# Current_Sense.net
KiCad netlist of a schematic drawn in Altium Designer
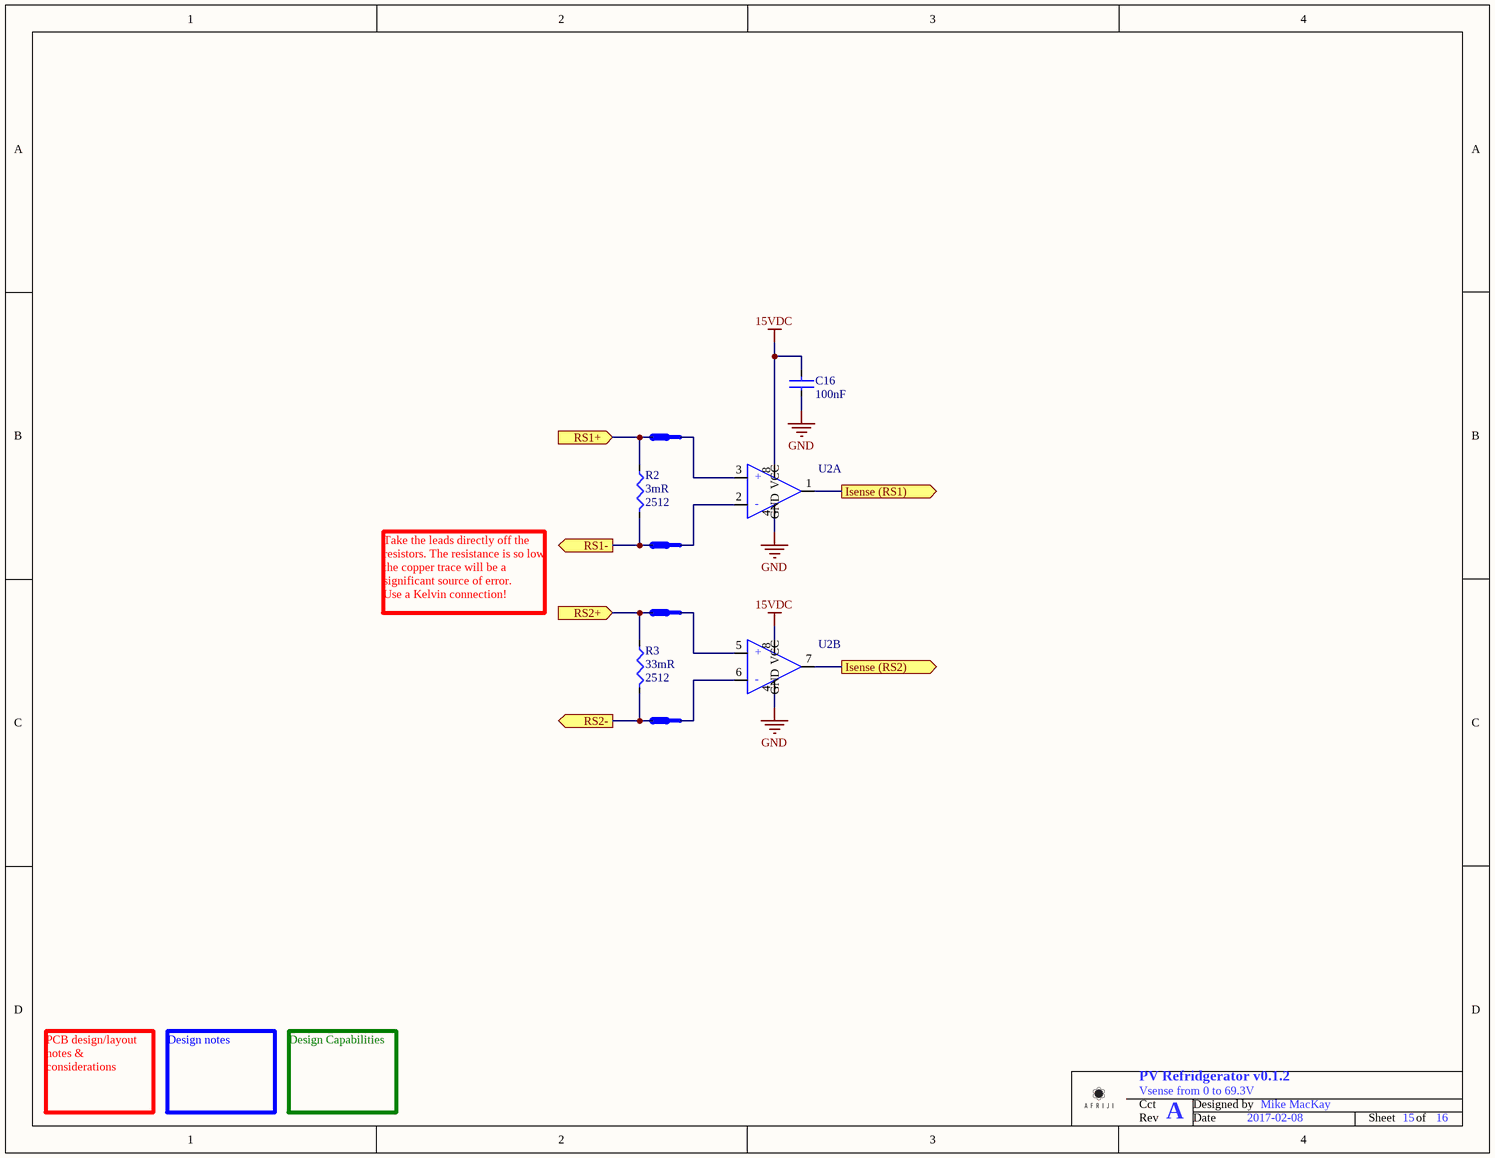
[diagram p0: Current Sense.SchDoc]

(export (version "E")
  (design (tool "Eeschema 10.0.6"))
  (components
    (comp (ref "C16")
      (value "100nF 0603 50V")
      (footprint "C0603 - Ceramic")
      (fields
        (field (name "MANUFACTURER") "Samsung Electro-Mechanics America, Inc")
        (field (name "MANUFACTURER PART NUMBER") "CL10B104KB8SFNC")
        (field (name "TOLERANCE") "±10%")
        (field (name "CAPACITANCE") "100nF")
      )
      (libsource (lib "Personal Library") (part "100nF 0603 50V"))
    )
    (comp (ref "NetTie3")
      (value "Net Tie")
      (footprint "Net tie (7/35 mil)")
      (description "Ties two nets together")
      (libsource (lib "Integrated Component Library") (part "Net Tie"))
    )
    (comp (ref "NetTie4")
      (value "Net Tie")
      (footprint "Net tie (7/7 mil)")
      (description "Ties two nets together")
      (libsource (lib "Integrated Component Library") (part "Net Tie"))
    )
    (comp (ref "NetTie5")
      (value "Net Tie")
      (footprint "Net tie (7/35 mil)")
      (description "Ties two nets together")
      (libsource (lib "Integrated Component Library") (part "Net Tie"))
    )
    (comp (ref "NetTie6")
      (value "Net Tie")
      (footprint "Net tie (7/7 mil)")
      (description "Ties two nets together")
      (libsource (lib "Integrated Component Library") (part "Net Tie"))
    )
    (comp (ref "R2")
      (value "3mR 2512 1%")
      (footprint "R2512")
      (fields
        (field (name "MANUFACTURER") "Yageo")
        (field (name "MANUFACTURER PART NUMBER") "PR2512FKF070R003L")
        (field (name "RESISTANCE (OHMS)") "3mR")
        (field (name "TOLERANCE") "±1%")
        (field (name "SUPPLIER DEVICE PACKAGE") "2512")
      )
      (libsource (lib "Local Library") (part "3mR 2512 1%"))
    )
    (comp (ref "R3")
      (value "33mR 2512 1%")
      (footprint "R2512")
      (fields
        (field (name "MANUFACTURER") "Yageo")
        (field (name "MANUFACTURER PART NUMBER") "RL2512FK-070R033L")
        (field (name "RESISTANCE (OHMS)") "33mR")
        (field (name "TOLERANCE") "±1%")
        (field (name "SUPPLIER DEVICE PACKAGE") "2512")
      )
      (libsource (lib "Local Library") (part "33mR 2512 1%"))
    )
    (comp (ref "U2")
      (value "Dual High Side Current Sense Amplifier")
      (footprint "SOIC-8 (3.9mm)")
      (fields
        (field (name "MANUFACTURER") "Maxim Integrated")
        (field (name "MANUFACTURER PART NUMBER") "MAX4377FASA+")
      )
      (libsource (lib "Local Library") (part "Dual High Side Current Sense Amplifier"))
    )
  )
  (nets
    (net (code "1") (name "/Isense (RS1)") (class "Default")
      (node (ref "U2") (pin "1") (pinfunction "Out_1") (pintype "passive"))
    )
    (net (code "2") (name "/Isense (RS2)") (class "Default")
      (node (ref "U2") (pin "7") (pinfunction "OUT2_7") (pintype "passive"))
    )
    (net (code "3") (name "/RS1+") (class "Default")
      (node (ref "NetTie3") (pin "2") (pinfunction "2_2") (pintype "passive"))
      (node (ref "R2") (pin "2") (pinfunction "2_2") (pintype "passive"))
    )
    (net (code "4") (name "/RS1-") (class "Default")
      (node (ref "NetTie4") (pin "2") (pinfunction "2_2") (pintype "passive"))
      (node (ref "R2") (pin "1") (pinfunction "1_1") (pintype "passive"))
    )
    (net (code "5") (name "/RS2+") (class "Default")
      (node (ref "NetTie5") (pin "2") (pinfunction "2_2") (pintype "passive"))
      (node (ref "R3") (pin "2") (pinfunction "2_2") (pintype "passive"))
    )
    (net (code "6") (name "/RS2-") (class "Default")
      (node (ref "NetTie6") (pin "2") (pinfunction "2_2") (pintype "passive"))
      (node (ref "R3") (pin "1") (pinfunction "1_1") (pintype "passive"))
    )
    (net (code "7") (name "15VDC") (class "Default")
      (node (ref "C16") (pin "1") (pinfunction "1_1") (pintype "passive"))
      (node (ref "U2") (pin "8") (pinfunction "VCC_8") (pintype "passive"))
    )
    (net (code "8") (name "GND") (class "Default")
      (node (ref "C16") (pin "2") (pinfunction "2_2") (pintype "passive"))
      (node (ref "U2") (pin "4") (pinfunction "GND_4") (pintype "passive"))
    )
    (net (code "9") (name "Net-(U2A-RS1+)") (class "Default")
      (node (ref "NetTie3") (pin "1") (pinfunction "1_1") (pintype "passive"))
      (node (ref "U2") (pin "3") (pinfunction "RS1+_3") (pintype "passive"))
    )
    (net (code "10") (name "Net-(U2A-RS1-)") (class "Default")
      (node (ref "NetTie4") (pin "1") (pinfunction "1_1") (pintype "passive"))
      (node (ref "U2") (pin "2") (pinfunction "RS1-_2") (pintype "passive"))
    )
    (net (code "11") (name "Net-(U2B-RS2+)") (class "Default")
      (node (ref "NetTie5") (pin "1") (pinfunction "1_1") (pintype "passive"))
      (node (ref "U2") (pin "5") (pinfunction "RS2+_5") (pintype "passive"))
    )
    (net (code "12") (name "Net-(U2B-RS2-)") (class "Default")
      (node (ref "NetTie6") (pin "1") (pinfunction "1_1") (pintype "passive"))
      (node (ref "U2") (pin "6") (pinfunction "RS2-_6") (pintype "passive"))
    )
  )
)
